# I2C_buttons.net
KiCad netlist of a schematic drawn in Altium Designer
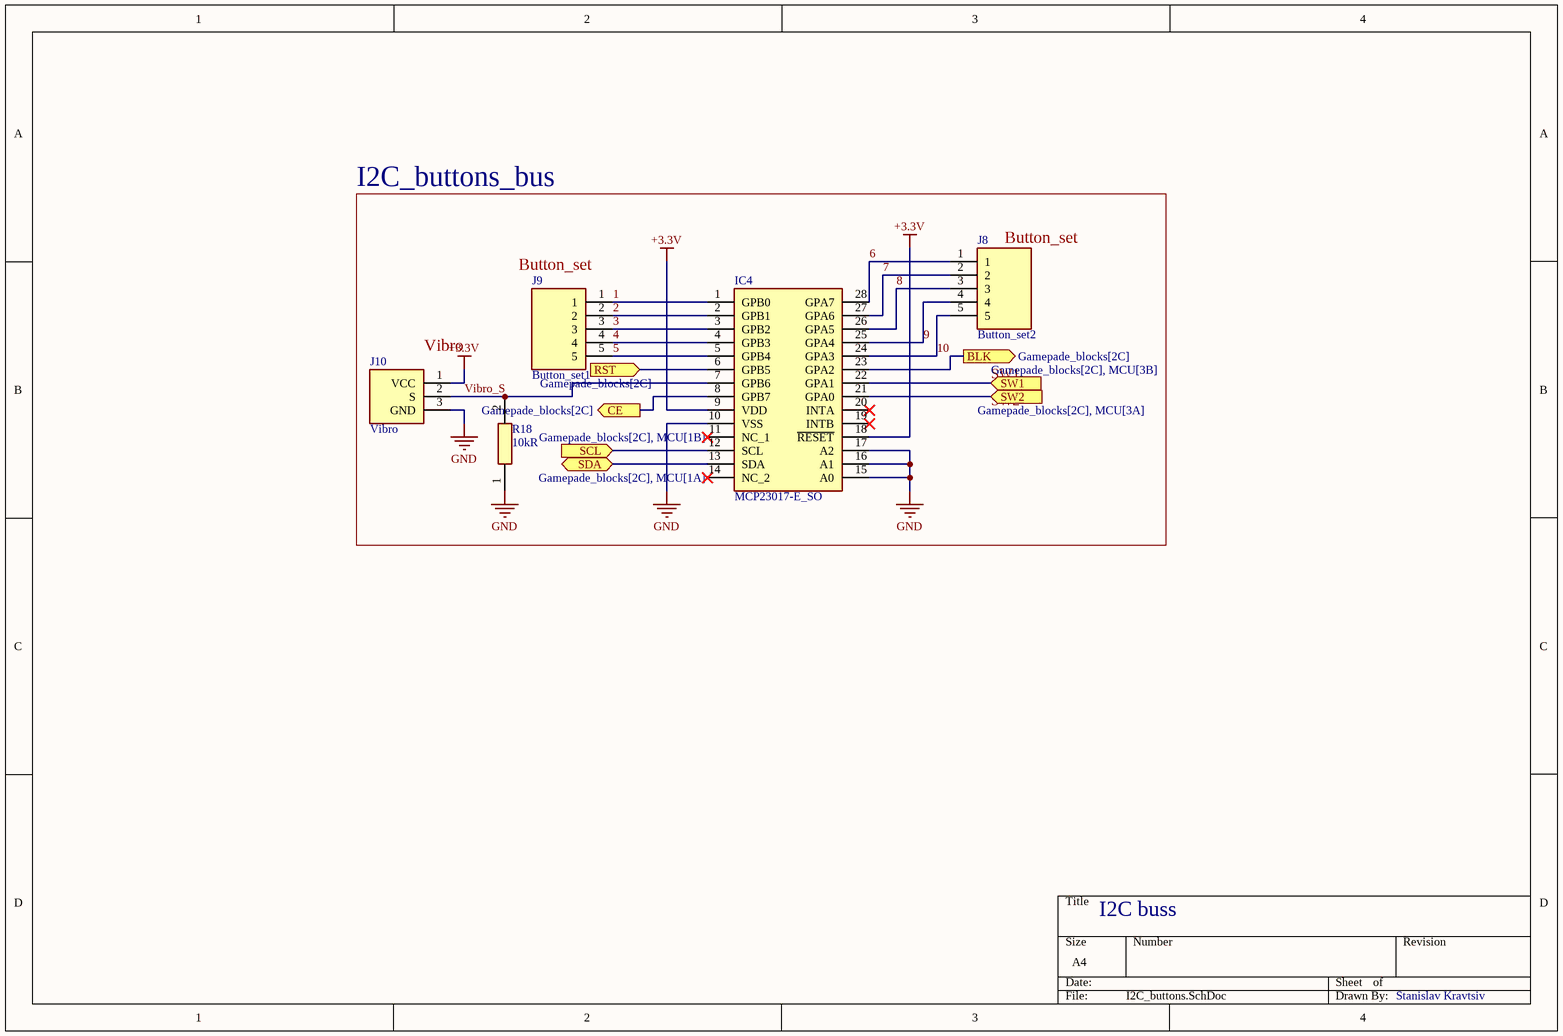
[diagram p0: I2C_buttons.SchDoc]

(export (version "E")
  (design (tool "Eeschema 10.0.6"))
  (components
    (comp (ref "IC4")
      (value "MCP23017-E_SO")
      (footprint "SamacSys:SOIC127P1030X265-28N")
      (description "Integrated Circuit")
      (fields
        (field (name "MANUFACTURER_PART_NUMBER") "MCP23017-E/SO")
        (field (name "MOUSER PART NUMBER") "579-MCP23017-E/SO")
      )
      (libsource (lib "*") (part "MCP23017-E_SO"))
    )
    (comp (ref "J8")
      (value "Button_set2")
      (footprint "1.25_JSH-GH_5")
      (description "Connector")
      (fields (field (name "MANUFACTURER_PART_NUMBER") "B5B-XH-AM (LF)(SN)"))
      (libsource (lib "") (part "B5B-XH-AM__LF__SN__1"))
    )
    (comp (ref "J9")
      (value "Button_set1")
      (footprint "1.25_JSH-GH_5")
      (description "Connector")
      (fields (field (name "MANUFACTURER_PART_NUMBER") "B5B-XH-AM (LF)(SN)"))
      (libsource (lib "Gamepad_schem_lib") (part "B5B-XH-AM__LF__SN_"))
    )
    (comp (ref "J10")
      (value "Vibro")
      (footprint "SamacSys:B3BXHALFSN")
      (description "Connector")
      (fields
        (field (name "MANUFACTURER_PART_NUMBER") "B3B-XH-A(LF)(SN)")
        (field (name "MOUSER PART NUMBER") "306-B3BXHALFSNP")
      )
      (libsource (lib "*") (part "B3B-XH-A_LF__SN_"))
    )
    (comp (ref "R18")
      (value "10kR")
      (footprint "SamacSys:RESC1608X55N")
      (description "Resistor")
      (fields (field (name "MANUFACTURER_PART_NUMBER") "RC0603FR0710KL"))
      (libsource (lib "SamacSys") (part "RC0603FR0710KL"))
    )
  )
  (nets
    (net (code "1") (name "+3.3V") (class "Default")
      (node (ref "IC4") (pin "18") (pinfunction "~{RESET}_18") (pintype "passive"))
      (node (ref "IC4") (pin "9") (pinfunction "VDD_9") (pintype "passive"))
      (node (ref "J10") (pin "1") (pinfunction "VCC_1") (pintype "passive"))
    )
    (net (code "2") (name "/1") (class "Default")
      (node (ref "IC4") (pin "1") (pinfunction "GPB0_1") (pintype "passive"))
      (node (ref "J9") (pin "1") (pinfunction "1_1") (pintype "passive"))
    )
    (net (code "3") (name "/2") (class "Default")
      (node (ref "IC4") (pin "2") (pinfunction "GPB1_2") (pintype "passive"))
      (node (ref "J9") (pin "2") (pinfunction "2_2") (pintype "passive"))
    )
    (net (code "4") (name "/3") (class "Default")
      (node (ref "IC4") (pin "3") (pinfunction "GPB2_3") (pintype "passive"))
      (node (ref "J9") (pin "3") (pinfunction "3_3") (pintype "passive"))
    )
    (net (code "5") (name "/4") (class "Default")
      (node (ref "IC4") (pin "4") (pinfunction "GPB3_4") (pintype "passive"))
      (node (ref "J9") (pin "4") (pinfunction "4_4") (pintype "passive"))
    )
    (net (code "6") (name "/5") (class "Default")
      (node (ref "IC4") (pin "5") (pinfunction "GPB4_5") (pintype "passive"))
      (node (ref "J9") (pin "5") (pinfunction "5_5") (pintype "passive"))
    )
    (net (code "7") (name "/6") (class "Default")
      (node (ref "IC4") (pin "28") (pinfunction "GPA7_28") (pintype "passive"))
      (node (ref "J8") (pin "1") (pinfunction "1_1") (pintype "passive"))
    )
    (net (code "8") (name "/7") (class "Default")
      (node (ref "IC4") (pin "27") (pinfunction "GPA6_27") (pintype "passive"))
      (node (ref "J8") (pin "2") (pinfunction "2_2") (pintype "passive"))
    )
    (net (code "9") (name "/8") (class "Default")
      (node (ref "IC4") (pin "26") (pinfunction "GPA5_26") (pintype "passive"))
      (node (ref "J8") (pin "3") (pinfunction "3_3") (pintype "passive"))
    )
    (net (code "10") (name "/9") (class "Default")
      (node (ref "IC4") (pin "25") (pinfunction "GPA4_25") (pintype "passive"))
      (node (ref "J8") (pin "4") (pinfunction "4_4") (pintype "passive"))
    )
    (net (code "11") (name "/10") (class "Default")
      (node (ref "IC4") (pin "24") (pinfunction "GPA3_24") (pintype "passive"))
      (node (ref "J8") (pin "5") (pinfunction "5_5") (pintype "passive"))
    )
    (net (code "12") (name "/BLK") (class "Default")
      (node (ref "IC4") (pin "23") (pinfunction "GPA2_23") (pintype "passive"))
    )
    (net (code "13") (name "/CE") (class "Default")
      (node (ref "IC4") (pin "8") (pinfunction "GPB7_8") (pintype "passive"))
    )
    (net (code "14") (name "/RST") (class "Default")
      (node (ref "IC4") (pin "6") (pinfunction "GPB5_6") (pintype "passive"))
    )
    (net (code "15") (name "/SCL") (class "Default")
      (node (ref "IC4") (pin "12") (pinfunction "SCL_12") (pintype "passive"))
    )
    (net (code "16") (name "/SDA") (class "Default")
      (node (ref "IC4") (pin "13") (pinfunction "SDA_13") (pintype "passive"))
    )
    (net (code "17") (name "/SW1") (class "Default")
      (node (ref "IC4") (pin "22") (pinfunction "GPA1_22") (pintype "passive"))
    )
    (net (code "18") (name "/SW2") (class "Default")
      (node (ref "IC4") (pin "21") (pinfunction "GPA0_21") (pintype "passive"))
    )
    (net (code "19") (name "/Vibro_S") (class "Default")
      (node (ref "IC4") (pin "7") (pinfunction "GPB6_7") (pintype "passive"))
      (node (ref "J10") (pin "2") (pinfunction "S_2") (pintype "passive"))
      (node (ref "R18") (pin "2") (pinfunction "2_2") (pintype "passive"))
    )
    (net (code "20") (name "GND") (class "Default")
      (node (ref "IC4") (pin "10") (pinfunction "VSS_10") (pintype "passive"))
      (node (ref "IC4") (pin "15") (pinfunction "A0_15") (pintype "passive"))
      (node (ref "IC4") (pin "16") (pinfunction "A1_16") (pintype "passive"))
      (node (ref "IC4") (pin "17") (pinfunction "A2_17") (pintype "passive"))
      (node (ref "J10") (pin "3") (pinfunction "GND_3") (pintype "passive"))
      (node (ref "R18") (pin "1") (pinfunction "1_1") (pintype "passive"))
    )
    (net (code "21") (name "unconnected-(IC4-INTA-Pad20)") (class "Default")
      (node (ref "IC4") (pin "20") (pinfunction "INTA_20") (pintype "passive+no_connect"))
    )
    (net (code "22") (name "unconnected-(IC4-INTB-Pad19)") (class "Default")
      (node (ref "IC4") (pin "19") (pinfunction "INTB_19") (pintype "passive+no_connect"))
    )
    (net (code "23") (name "unconnected-(IC4-NC_1-Pad11)") (class "Default")
      (node (ref "IC4") (pin "11") (pinfunction "NC_1_11") (pintype "passive+no_connect"))
    )
    (net (code "24") (name "unconnected-(IC4-NC_2-Pad14)") (class "Default")
      (node (ref "IC4") (pin "14") (pinfunction "NC_2_14") (pintype "passive+no_connect"))
    )
  )
)
